# kuramoto7.net
KiCad netlist of a schematic drawn in EAGLE
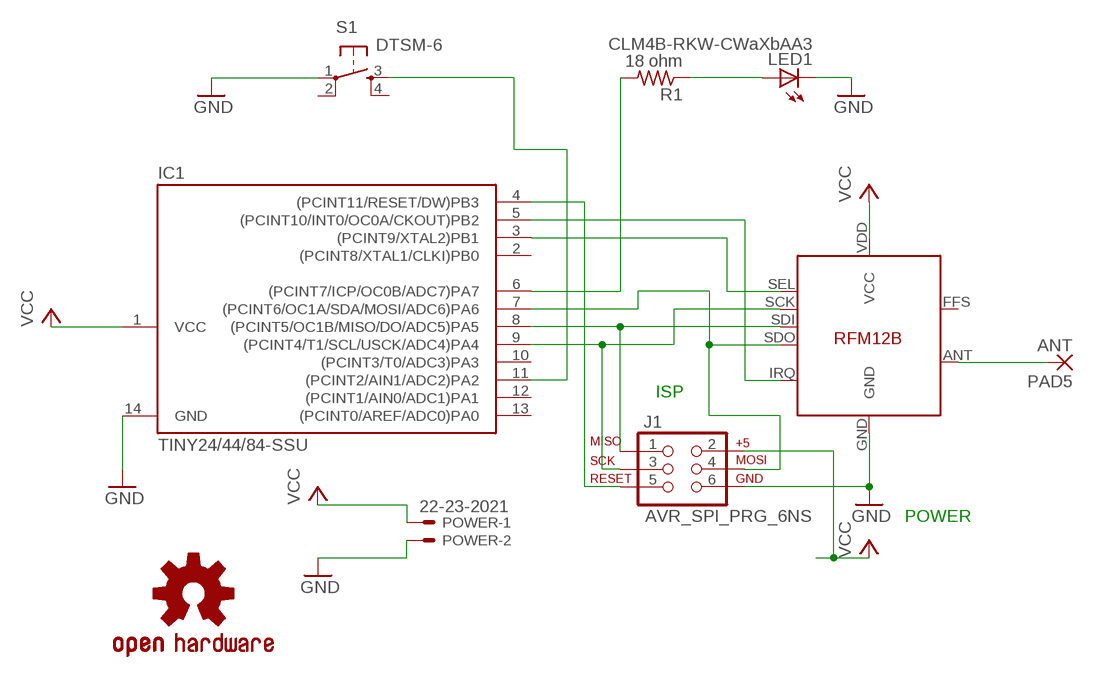
[diagram p0: schematic, sheet 1]

(export (version "E")
  (design (tool "Eeschema 10.0.6"))
  (components
    (comp (ref "IC1")
      (value "TINY24/44/84-SSU")
      (footprint "eagle-import:SOIC14")
      (libsource (lib "eagle-import") (part "TINY24/44/84-SSU"))
    )
    (comp (ref "J1")
      (value "AVR_SPI_PRG_6NS")
      (footprint "eagle-import:2X3-NS")
      (libsource (lib "eagle-import") (part "AVR_SPI_PRG_6NS"))
    )
    (comp (ref "LED1")
      (value "CLM4B-RKW-CWaXbAA3")
      (footprint "eagle-import:P-LCC-4")
      (libsource (lib "eagle-import") (part "LEDP-LCC-4"))
    )
    (comp (ref "PAD5")
      (value "ANT")
      (footprint "eagle-import:2,54_1,0")
      (libsource (lib "eagle-import") (part "WIREPAD2,54/1,0"))
    )
    (comp (ref "POWER")
      (value "22-23-2021")
      (footprint "eagle-import:22-23-2021")
      (fields (field (name "MF") "MOLEX"))
      (libsource (lib "eagle-import") (part "22-23-2021"))
    )
    (comp (ref "R1")
      (value "18 ohm")
      (footprint "eagle-import:R0805")
      (libsource (lib "eagle-import") (part "R-US_R0805"))
    )
    (comp (ref "RFM12B")
      (value "RFM12BN")
      (footprint "eagle-import:RFM12B-NARROW")
      (libsource (lib "eagle-import") (part "RFM12BN"))
    )
    (comp (ref "S1")
      (value "DTSM-6")
      (footprint "eagle-import:DTSM-6")
      (libsource (lib "eagle-import") (part "DTSM-6"))
    )
    (comp (ref "U$1")
      (value "OSHW-LOGOS")
      (footprint "eagle-import:OSHW-LOGO-S")
      (libsource (lib "eagle-import") (part "OSHW-LOGOS"))
    )
  )
  (nets
    (net (code "1") (name "GND") (class "Default")
      (node (ref "IC1") (pin "14") (pinfunction "GND_14") (pintype "power_in"))
      (node (ref "J1") (pin "6") (pinfunction "6_6") (pintype "passive"))
      (node (ref "LED1") (pin "C@4") (pinfunction "C_C@4") (pintype "passive"))
      (node (ref "POWER") (pin "2") (pinfunction "S_2") (pintype "passive"))
      (node (ref "RFM12B") (pin "GND") (pinfunction "GND_GND") (pintype "power_in"))
      (node (ref "S1") (pin "1") (pinfunction "1_1") (pintype "passive"))
    )
    (net (code "2") (name "Net-(IC1-(PCINT2{slash}AIN1{slash}ADC2)PA2)") (class "Default")
      (node (ref "IC1") (pin "11") (pinfunction "(PCINT2/AIN1/ADC2)PA2_11") (pintype "bidirectional"))
      (node (ref "S1") (pin "3") (pinfunction "3_3") (pintype "passive"))
    )
    (net (code "3") (name "Net-(IC1-(PCINT4{slash}T1{slash}SCL{slash}USCK{slash}ADC4)PA4)") (class "Default")
      (node (ref "IC1") (pin "9") (pinfunction "(PCINT4/T1/SCL/USCK/ADC4)PA4_9") (pintype "bidirectional"))
      (node (ref "J1") (pin "3") (pinfunction "3_3") (pintype "passive"))
      (node (ref "RFM12B") (pin "SCK") (pinfunction "SCK_SCK") (pintype "input"))
    )
    (net (code "4") (name "Net-(IC1-(PCINT5{slash}OC1B{slash}MISO{slash}DO{slash}ADC5)PA5)") (class "Default")
      (node (ref "IC1") (pin "8") (pinfunction "(PCINT5/OC1B/MISO/DO/ADC5)PA5_8") (pintype "bidirectional"))
      (node (ref "J1") (pin "1") (pinfunction "1_1") (pintype "passive"))
      (node (ref "RFM12B") (pin "SDI") (pinfunction "SDI_SDI") (pintype "input"))
    )
    (net (code "5") (name "Net-(IC1-(PCINT6{slash}OC1A{slash}SDA{slash}MOSI{slash}ADC6)PA6)") (class "Default")
      (node (ref "IC1") (pin "7") (pinfunction "(PCINT6/OC1A/SDA/MOSI/ADC6)PA6_7") (pintype "bidirectional"))
      (node (ref "J1") (pin "4") (pinfunction "4_4") (pintype "passive"))
      (node (ref "RFM12B") (pin "SDO") (pinfunction "SDO_SDO") (pintype "output"))
    )
    (net (code "6") (name "Net-(IC1-(PCINT7{slash}ICP{slash}OC0B{slash}ADC7)PA7)") (class "Default")
      (node (ref "IC1") (pin "6") (pinfunction "(PCINT7/ICP/OC0B/ADC7)PA7_6") (pintype "bidirectional"))
      (node (ref "R1") (pin "2") (pinfunction "2_2") (pintype "passive"))
    )
    (net (code "7") (name "Net-(IC1-(PCINT9{slash}XTAL2)PB1)") (class "Default")
      (node (ref "IC1") (pin "3") (pinfunction "(PCINT9/XTAL2)PB1_3") (pintype "bidirectional"))
      (node (ref "RFM12B") (pin "SEL") (pinfunction "SEL_SEL") (pintype "input"))
    )
    (net (code "8") (name "Net-(IC1-(PCINT10{slash}INT0{slash}OC0A{slash}CKOUT)PB2)") (class "Default")
      (node (ref "IC1") (pin "5") (pinfunction "(PCINT10/INT0/OC0A/CKOUT)PB2_5") (pintype "bidirectional"))
      (node (ref "RFM12B") (pin "IRQ") (pinfunction "IRQ_IRQ") (pintype "open_collector"))
    )
    (net (code "9") (name "Net-(IC1-(PCINT11{slash}RESET{slash}DW)PB3)") (class "Default")
      (node (ref "IC1") (pin "4") (pinfunction "(PCINT11/RESET/DW)PB3_4") (pintype "bidirectional"))
      (node (ref "J1") (pin "5") (pinfunction "5_5") (pintype "passive"))
    )
    (net (code "10") (name "Net-(LED1-PadA)") (class "Default")
      (node (ref "LED1") (pin "A") (pinfunction "A_A") (pintype "passive"))
      (node (ref "R1") (pin "1") (pinfunction "1_1") (pintype "passive"))
    )
    (net (code "11") (name "Net-(PAD5-P)") (class "Default")
      (node (ref "PAD5") (pin "1") (pinfunction "P_1") (pintype "passive"))
      (node (ref "RFM12B") (pin "ANT") (pinfunction "ANT_ANT") (pintype "passive"))
    )
    (net (code "12") (name "VCC") (class "Default")
      (node (ref "IC1") (pin "1") (pinfunction "VCC_1") (pintype "power_in"))
      (node (ref "J1") (pin "2") (pinfunction "2_2") (pintype "passive"))
      (node (ref "POWER") (pin "1") (pinfunction "S_1") (pintype "passive"))
      (node (ref "RFM12B") (pin "VDD") (pinfunction "VCC_VDD") (pintype "power_in"))
    )
    (net (code "13") (name "unconnected-(IC1-(PCINT0{slash}AREF{slash}ADC0)PA0-Pad13)") (class "Default")
      (node (ref "IC1") (pin "13") (pinfunction "(PCINT0/AREF/ADC0)PA0_13") (pintype "bidirectional"))
    )
    (net (code "14") (name "unconnected-(IC1-(PCINT1{slash}AIN0{slash}ADC1)PA1-Pad12)") (class "Default")
      (node (ref "IC1") (pin "12") (pinfunction "(PCINT1/AIN0/ADC1)PA1_12") (pintype "bidirectional"))
    )
    (net (code "15") (name "unconnected-(IC1-(PCINT3{slash}T0{slash}ADC3)PA3-Pad10)") (class "Default")
      (node (ref "IC1") (pin "10") (pinfunction "(PCINT3/T0/ADC3)PA3_10") (pintype "bidirectional"))
    )
    (net (code "16") (name "unconnected-(IC1-(PCINT8{slash}XTAL1{slash}CLKI)PB0-Pad2)") (class "Default")
      (node (ref "IC1") (pin "2") (pinfunction "(PCINT8/XTAL1/CLKI)PB0_2") (pintype "bidirectional"))
    )
    (net (code "17") (name "unconnected-(RFM12B-PadFFS)") (class "Default")
      (node (ref "RFM12B") (pin "FFS") (pinfunction "FFS_FFS") (pintype "bidirectional"))
    )
    (net (code "18") (name "unconnected-(S1-Pad2)") (class "Default")
      (node (ref "S1") (pin "2") (pinfunction "2_2") (pintype "passive"))
    )
    (net (code "19") (name "unconnected-(S1-Pad4)") (class "Default")
      (node (ref "S1") (pin "4") (pinfunction "4_4") (pintype "passive"))
    )
  )
)
